# T_TV1_0.net
KiCad netlist of a schematic drawn in EAGLE
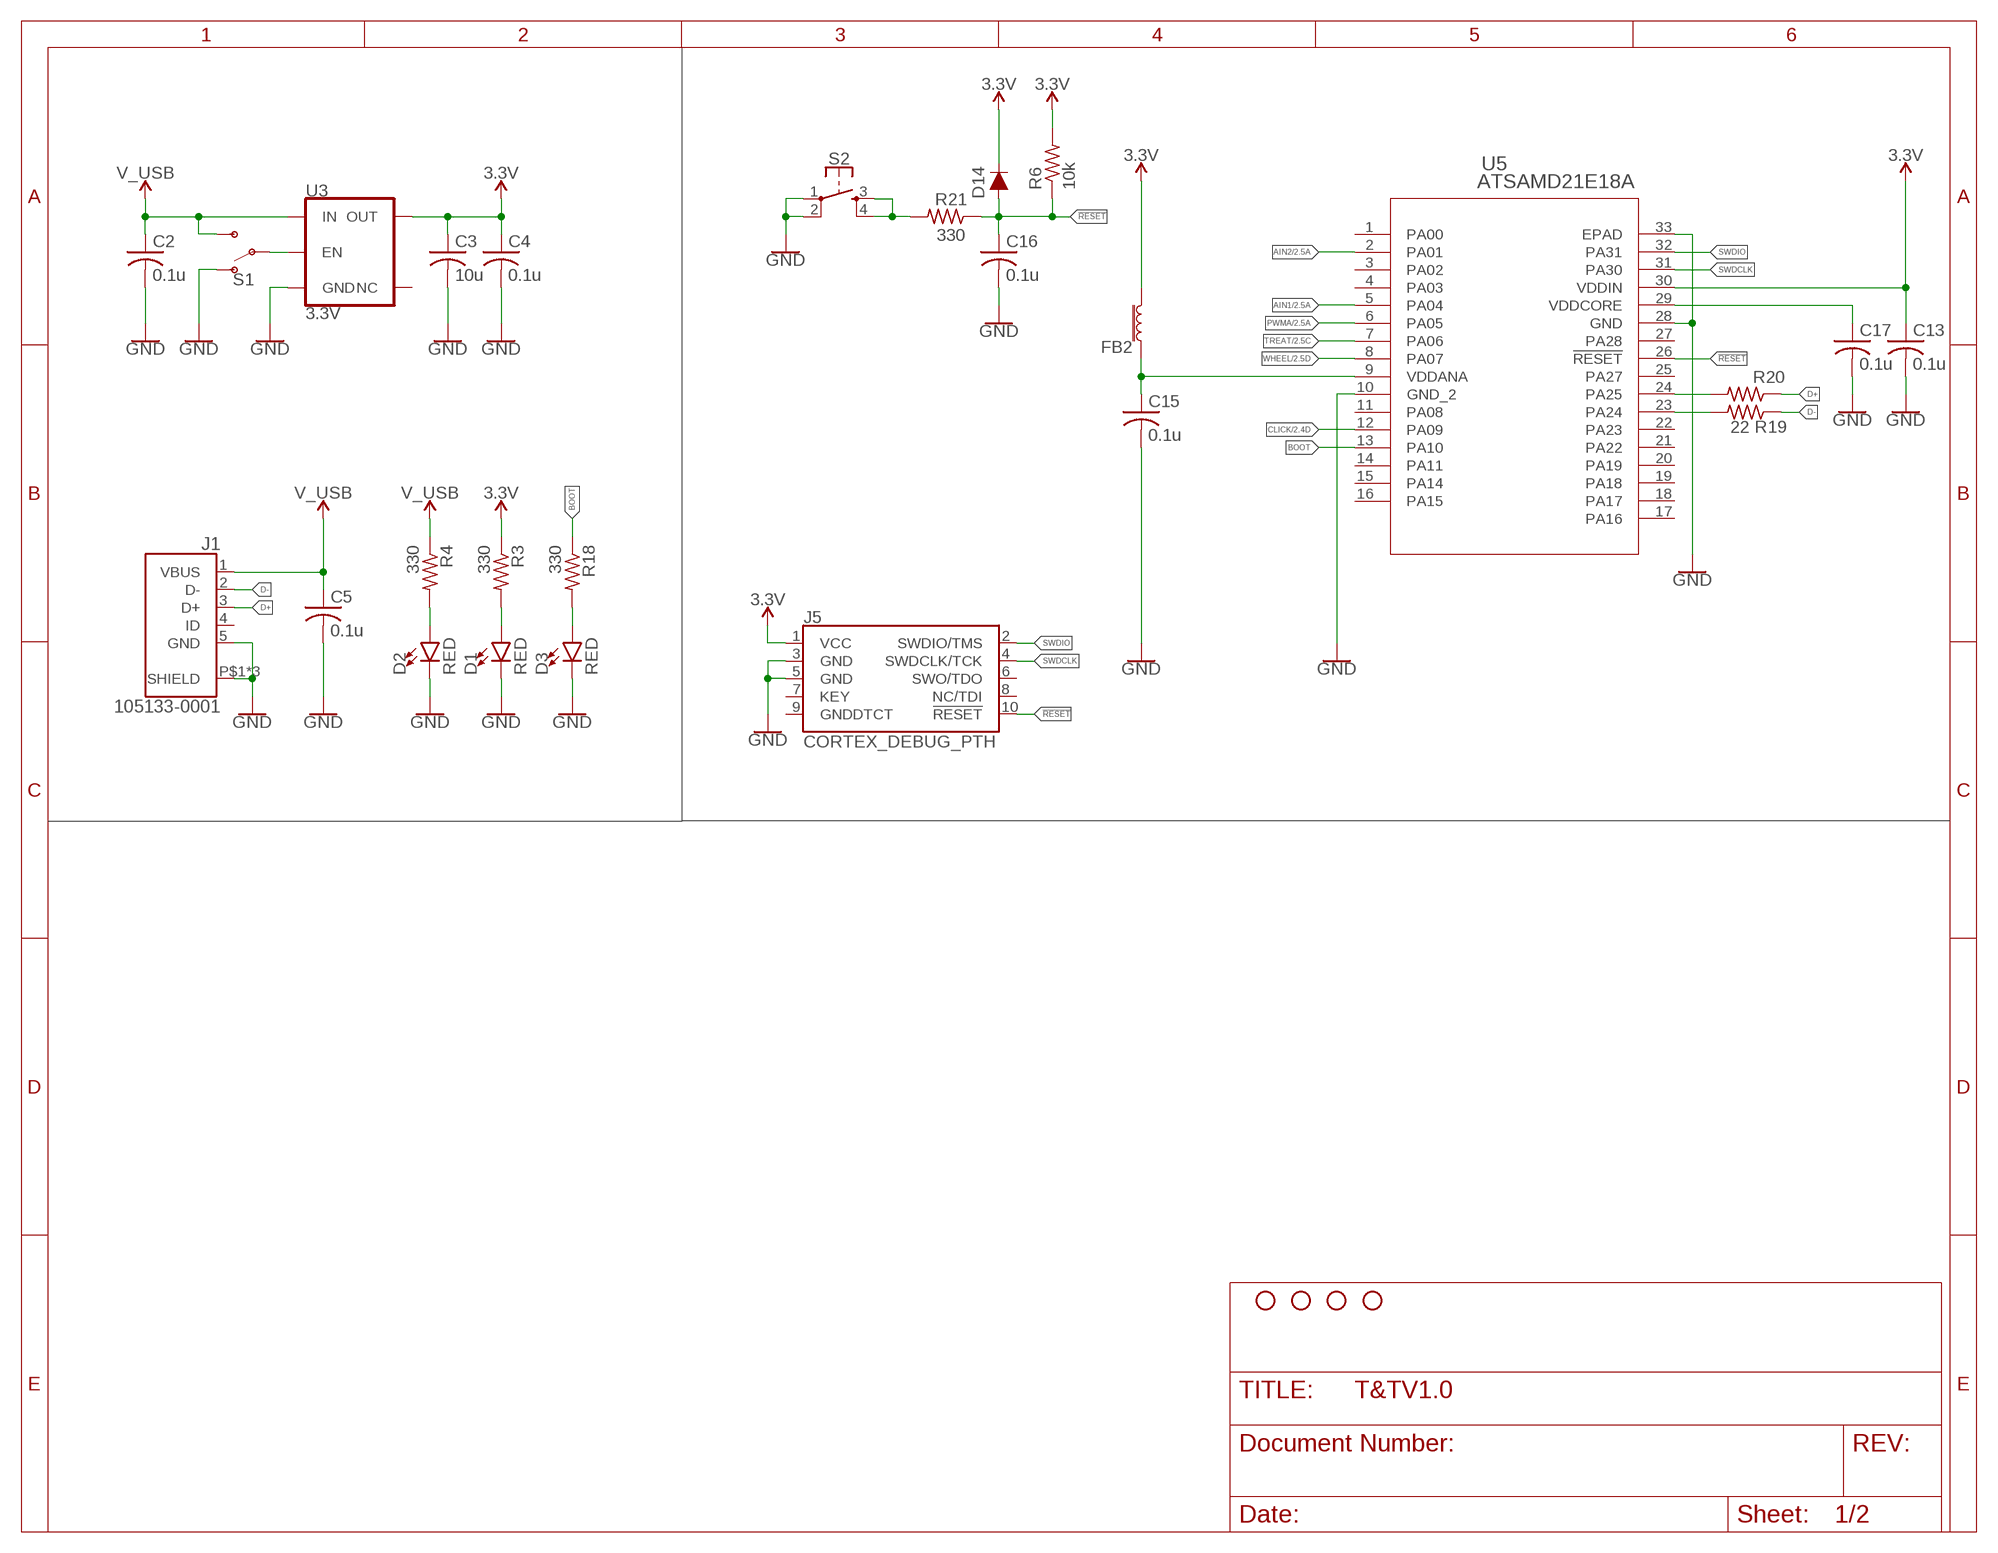
[diagram p0: schematic, sheet 1]
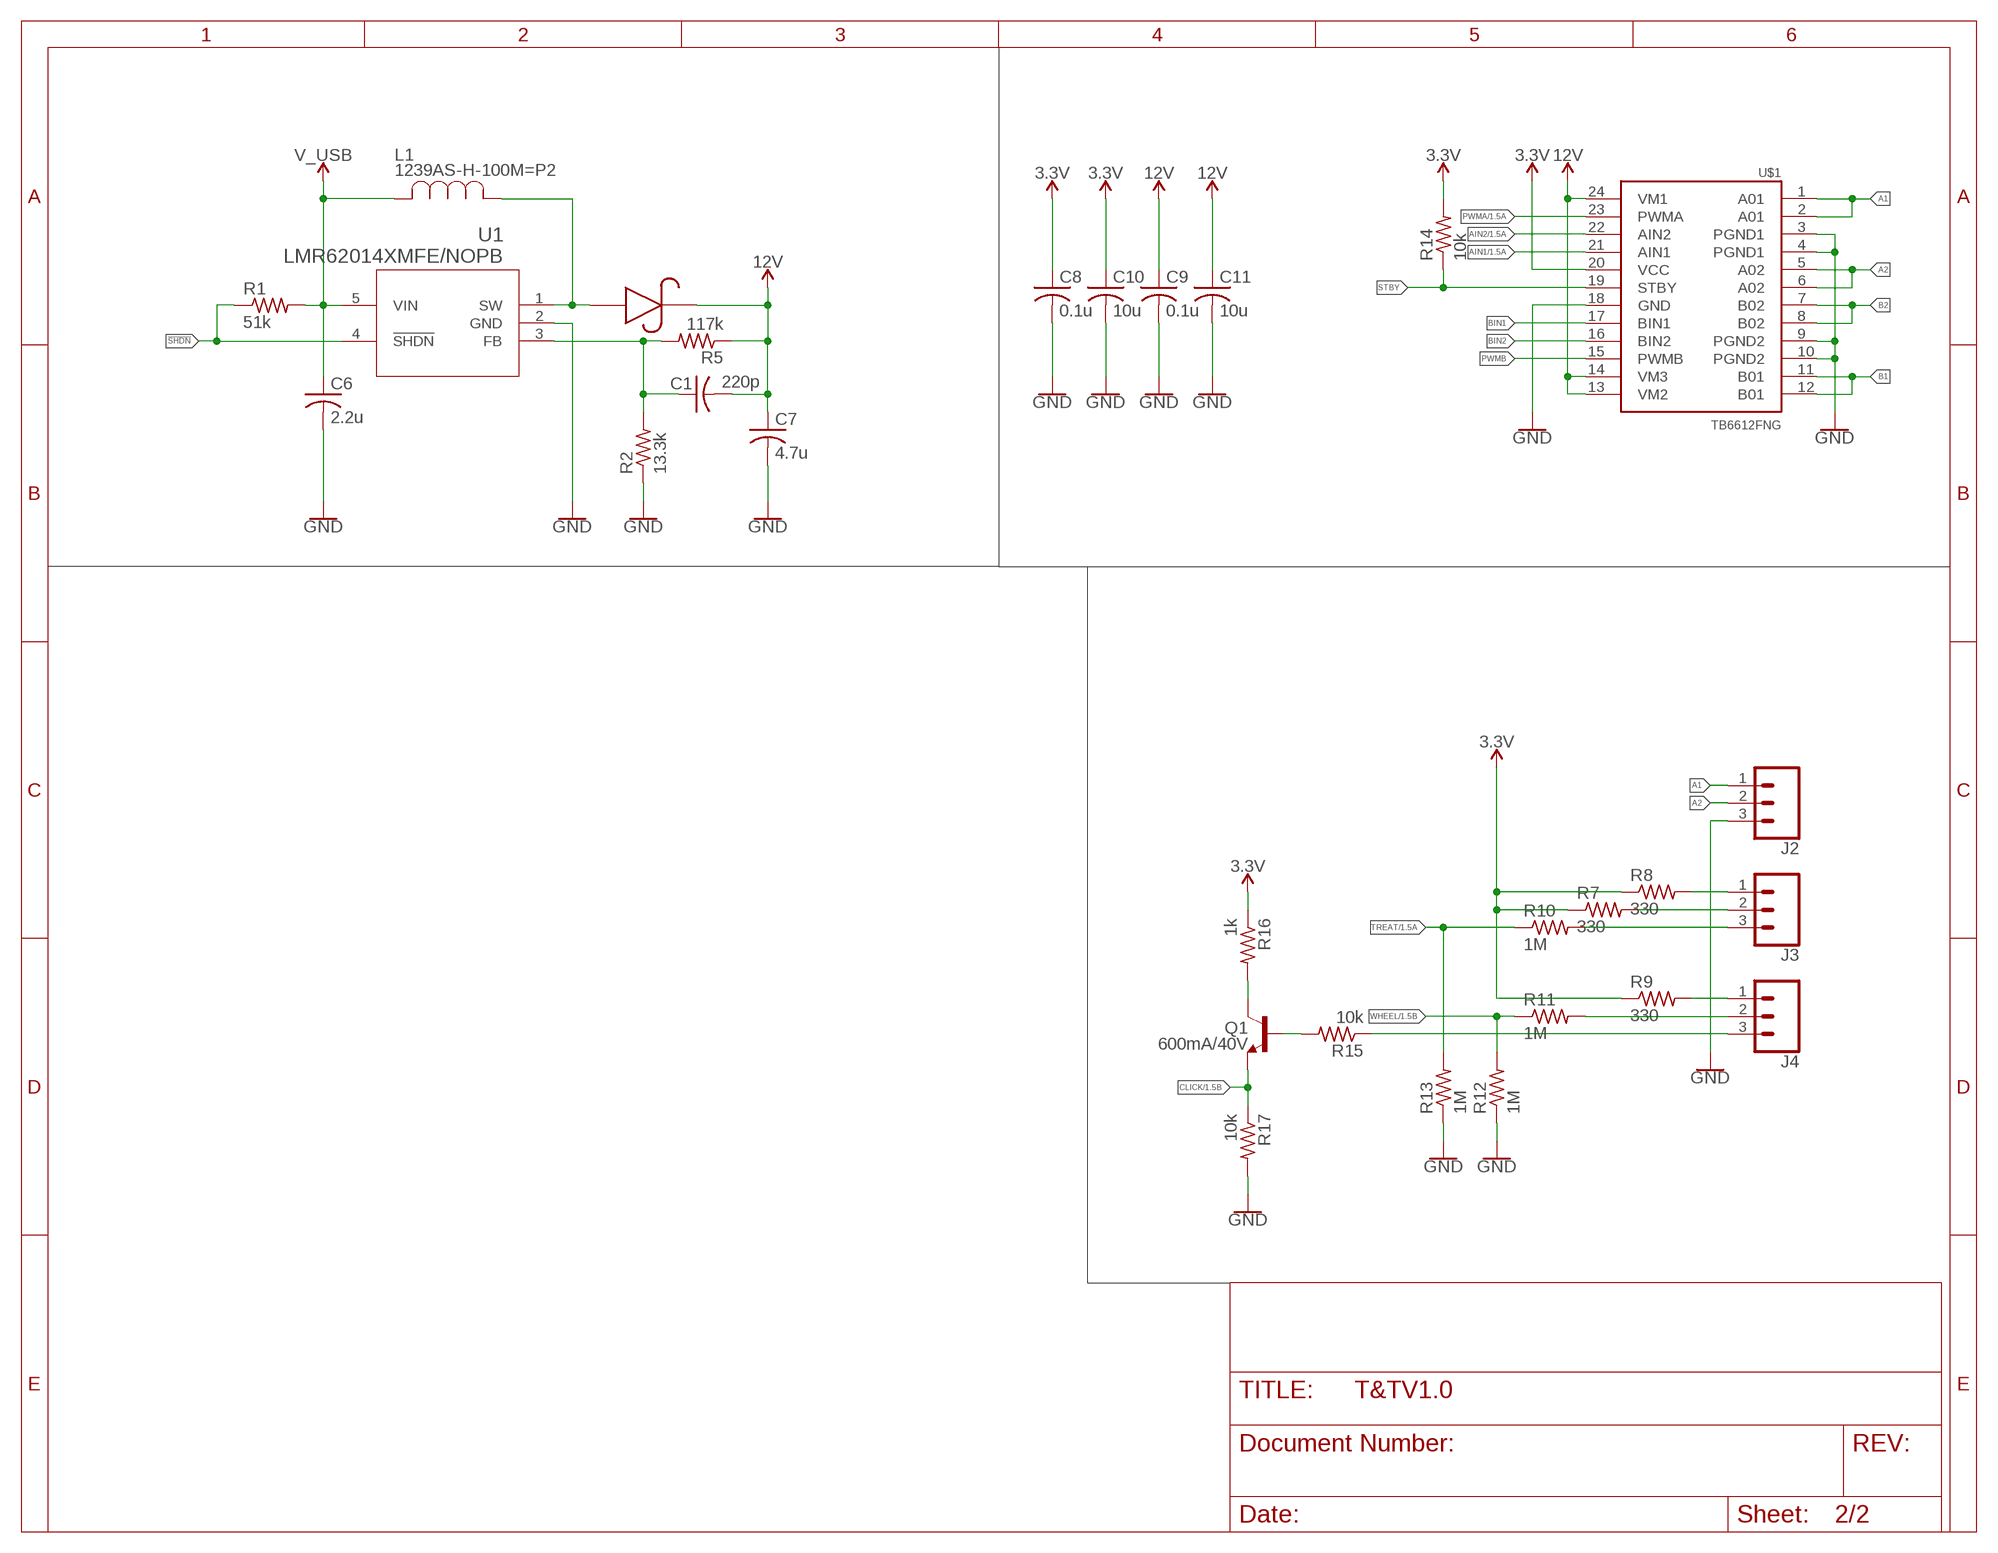
[diagram p1: schematic, sheet 2]

(export (version "E")
  (design (tool "Eeschema 10.0.6"))
  (components
    (comp (ref "C2")
      (value "0.1u")
      (footprint "eagle-import:C0603K")
      (libsource (lib "eagle-import") (part "C-USC0603K"))
    )
    (comp (ref "C3")
      (value "10u")
      (footprint "eagle-import:C1206")
      (libsource (lib "eagle-import") (part "C-USC1206"))
    )
    (comp (ref "C4")
      (value "0.1u")
      (footprint "eagle-import:C0603K")
      (libsource (lib "eagle-import") (part "C-USC0603K"))
    )
    (comp (ref "C5")
      (value "0.1u")
      (footprint "eagle-import:C0603K")
      (libsource (lib "eagle-import") (part "C-USC0603K"))
    )
    (comp (ref "C13")
      (value "0.1u")
      (footprint "eagle-import:C0603K")
      (libsource (lib "eagle-import") (part "C-USC0603K"))
    )
    (comp (ref "C15")
      (value "0.1u")
      (footprint "eagle-import:C0603K")
      (libsource (lib "eagle-import") (part "C-USC0603K"))
    )
    (comp (ref "C16")
      (value "0.1u")
      (footprint "eagle-import:C0603K")
      (libsource (lib "eagle-import") (part "C-USC0603K"))
    )
    (comp (ref "C17")
      (value "0.1u")
      (footprint "eagle-import:C0603K")
      (libsource (lib "eagle-import") (part "C-USC0603K"))
    )
    (comp (ref "D1")
      (value "RED")
      (footprint "eagle-import:LED-0603")
      (libsource (lib "eagle-import") (part "LED-RED0603"))
    )
    (comp (ref "D2")
      (value "RED")
      (footprint "eagle-import:LED-0603")
      (libsource (lib "eagle-import") (part "LED-RED0603"))
    )
    (comp (ref "D3")
      (value "RED")
      (footprint "eagle-import:LED-0603")
      (libsource (lib "eagle-import") (part "LED-RED0603"))
    )
    (comp (ref "D14")
      (value "250mA/100V")
      (footprint "eagle-import:SOD-323")
      (libsource (lib "eagle-import") (part "DIODE-BAS16J"))
    )
    (comp (ref "FB2")
      (value "30Ω/1.8A")
      (footprint "eagle-import:0603")
      (libsource (lib "eagle-import") (part "FERRITE_BEAD-0603"))
    )
    (comp (ref "H1")
      (value "STAND-OFF")
      (footprint "eagle-import:STAND-OFF")
      (libsource (lib "eagle-import") (part "STAND-OFF"))
    )
    (comp (ref "H2")
      (value "STAND-OFF")
      (footprint "eagle-import:STAND-OFF")
      (libsource (lib "eagle-import") (part "STAND-OFF"))
    )
    (comp (ref "H3")
      (value "STAND-OFF")
      (footprint "eagle-import:STAND-OFF")
      (libsource (lib "eagle-import") (part "STAND-OFF"))
    )
    (comp (ref "H4")
      (value "STAND-OFF")
      (footprint "eagle-import:STAND-OFF")
      (libsource (lib "eagle-import") (part "STAND-OFF"))
    )
    (comp (ref "J1")
      (value "105133-0001")
      (footprint "eagle-import:MOLEX_105133-0001")
      (fields
        (field (name "DIGI-KEY_PART_NUMBER") "WM9734CT-ND")
        (field (name "MF") "Molex")
        (field (name "MP") "1051330001")
      )
      (libsource (lib "eagle-import") (part "105133-0001"))
    )
    (comp (ref "J5")
      (value "CORTEX_DEBUG_PTH")
      (footprint "eagle-import:2X5-PTH-1.27MM")
      (libsource (lib "eagle-import") (part "CORTEX_DEBUG_PTH"))
    )
    (comp (ref "R3")
      (value "330")
      (footprint "eagle-import:R0603")
      (libsource (lib "eagle-import") (part "R-US_R0603"))
    )
    (comp (ref "R4")
      (value "330")
      (footprint "eagle-import:R0603")
      (libsource (lib "eagle-import") (part "R-US_R0603"))
    )
    (comp (ref "R6")
      (value "10k")
      (footprint "eagle-import:R0603")
      (libsource (lib "eagle-import") (part "R-US_R0603"))
    )
    (comp (ref "R18")
      (value "330")
      (footprint "eagle-import:R0603")
      (libsource (lib "eagle-import") (part "R-US_R0603"))
    )
    (comp (ref "R19")
      (value "22")
      (footprint "eagle-import:R0603")
      (libsource (lib "eagle-import") (part "R-US_R0603"))
    )
    (comp (ref "R20")
      (value "22")
      (footprint "eagle-import:R0603")
      (libsource (lib "eagle-import") (part "R-US_R0603"))
    )
    (comp (ref "R21")
      (value "330")
      (footprint "eagle-import:R0603")
      (libsource (lib "eagle-import") (part "R-US_R0603"))
    )
    (comp (ref "S1")
      (value "SWITCH-SPDT-SMD-RIGHT-ANGLE")
      (footprint "eagle-import:SWITCH_SPST_SMD_A")
      (libsource (lib "eagle-import") (part "SWITCH-SPDT-SMD-RIGHT-ANGLE"))
    )
    (comp (ref "S2")
      (value "MOMENTARY-SWITCH-SPST-2-SMD-5.2MM")
      (footprint "eagle-import:TACTILE_SWITCH_SMD_5.2MM")
      (libsource (lib "eagle-import") (part "MOMENTARY-SWITCH-SPST-2-SMD-5.2MM"))
    )
    (comp (ref "U3")
      (value "3.3V")
      (footprint "eagle-import:SOT23-5")
      (libsource (lib "eagle-import") (part "V_REG_AP2112K-3.3V"))
    )
    (comp (ref "U5")
      (value "ATSAMD21E18A")
      (footprint "eagle-import:QFN32_5X5MC")
      (fields
        (field (name "MANUFACTURER_PART_NUMBER") "ATSAMD21E18A-MUT")
        (field (name "COPYRIGHT") "Copyright (C) 2018 Accelerated Designs. All rights reserved")
      )
      (libsource (lib "eagle-import") (part "ATSAMD21E18A-MUT"))
    )
    (comp (ref "C1")
      (value "220p")
      (footprint "eagle-import:C0603")
      (libsource (lib "eagle-import") (part "adafruit_420_C-USC0603"))
    )
    (comp (ref "C6")
      (value "2.2u")
      (footprint "eagle-import:C0603")
      (libsource (lib "eagle-import") (part "adafruit_420_C-USC0603"))
    )
    (comp (ref "C7")
      (value "4.7u")
      (footprint "eagle-import:C0603")
      (libsource (lib "eagle-import") (part "adafruit_420_C-USC0603"))
    )
    (comp (ref "C8")
      (value "0.1u")
      (footprint "eagle-import:C0603")
      (libsource (lib "eagle-import") (part "adafruit_420_C-USC0603"))
    )
    (comp (ref "C9")
      (value "0.1u")
      (footprint "eagle-import:C0603")
      (libsource (lib "eagle-import") (part "adafruit_420_C-USC0603"))
    )
    (comp (ref "C10")
      (value "10u")
      (footprint "eagle-import:C1206")
      (libsource (lib "eagle-import") (part "C-USC1206"))
    )
    (comp (ref "C11")
      (value "10u")
      (footprint "eagle-import:C1206")
      (libsource (lib "eagle-import") (part "C-USC1206"))
    )
    (comp (ref "J2")
      (value "CONN_03SCREW-NS")
      (footprint "eagle-import:SCREWTERMINAL-3.5MM-3-NS")
      (libsource (lib "eagle-import") (part "CONN_03SCREW-NS"))
    )
    (comp (ref "J3")
      (value "CONN_03SCREW-NS")
      (footprint "eagle-import:SCREWTERMINAL-3.5MM-3-NS")
      (libsource (lib "eagle-import") (part "CONN_03SCREW-NS"))
    )
    (comp (ref "J4")
      (value "CONN_03SCREW-NS")
      (footprint "eagle-import:SCREWTERMINAL-3.5MM-3-NS")
      (libsource (lib "eagle-import") (part "CONN_03SCREW-NS"))
    )
    (comp (ref "L1")
      (value "1239AS-H-100M=P2")
      (footprint "eagle-import:IND_DFE252012C")
      (fields (field (name "COPYRIGHT") "Copyright (C) 2016 Accelerated Designs. All rights reserved"))
      (libsource (lib "eagle-import") (part "1239AS-H-100M=P2"))
    )
    (comp (ref "Q1")
      (value "600mA/40V")
      (footprint "eagle-import:SOT23-3")
      (libsource (lib "eagle-import") (part "TRANS_NPN-MMBT2222AL"))
    )
    (comp (ref "R1")
      (value "51k")
      (footprint "eagle-import:R0603")
      (libsource (lib "eagle-import") (part "adafruit_420_R-US_R0603"))
    )
    (comp (ref "R2")
      (value "13.3k")
      (footprint "eagle-import:R0603")
      (libsource (lib "eagle-import") (part "adafruit_420_R-US_R0603"))
    )
    (comp (ref "R5")
      (value "117k")
      (footprint "eagle-import:R0603")
      (libsource (lib "eagle-import") (part "adafruit_420_R-US_R0603"))
    )
    (comp (ref "R7")
      (value "330")
      (footprint "eagle-import:R0603")
      (libsource (lib "eagle-import") (part "adafruit_420_R-US_R0603"))
    )
    (comp (ref "R8")
      (value "330")
      (footprint "eagle-import:R0603")
      (libsource (lib "eagle-import") (part "adafruit_420_R-US_R0603"))
    )
    (comp (ref "R9")
      (value "330")
      (footprint "eagle-import:R0603")
      (libsource (lib "eagle-import") (part "adafruit_420_R-US_R0603"))
    )
    (comp (ref "R10")
      (value "1M")
      (footprint "eagle-import:R0603")
      (libsource (lib "eagle-import") (part "adafruit_420_R-US_R0603"))
    )
    (comp (ref "R11")
      (value "1M")
      (footprint "eagle-import:R0603")
      (libsource (lib "eagle-import") (part "adafruit_420_R-US_R0603"))
    )
    (comp (ref "R12")
      (value "1M")
      (footprint "eagle-import:R0603")
      (libsource (lib "eagle-import") (part "adafruit_420_R-US_R0603"))
    )
    (comp (ref "R13")
      (value "1M")
      (footprint "eagle-import:R0603")
      (libsource (lib "eagle-import") (part "adafruit_420_R-US_R0603"))
    )
    (comp (ref "R14")
      (value "10k")
      (footprint "eagle-import:R0603")
      (libsource (lib "eagle-import") (part "adafruit_420_R-US_R0603"))
    )
    (comp (ref "R15")
      (value "10k")
      (footprint "eagle-import:R0603")
      (libsource (lib "eagle-import") (part "adafruit_420_R-US_R0603"))
    )
    (comp (ref "R16")
      (value "1k")
      (footprint "eagle-import:R0603")
      (libsource (lib "eagle-import") (part "adafruit_420_R-US_R0603"))
    )
    (comp (ref "R17")
      (value "10k")
      (footprint "eagle-import:R0603")
      (libsource (lib "eagle-import") (part "adafruit_420_R-US_R0603"))
    )
    (comp (ref "U$1")
      (value "TB6612FNG")
      (footprint "eagle-import:SSOP24")
      (libsource (lib "eagle-import") (part "TB6612FNG"))
    )
    (comp (ref "U1")
      (value "LMR62014XMFE/NOPB")
      (footprint "eagle-import:MF05A")
      (fields (field (name "MANUFACTURER") "Texas Instruments"))
      (libsource (lib "eagle-import") (part "LMR62014XMFE/NOPB"))
    )
    (comp (ref "U4")
      (value "MBR0520")
      (footprint "eagle-import:SOD-123")
      (fields (field (name "MANUFACTURER_PART_NUMBER") "MBR0520LT1G"))
      (libsource (lib "eagle-import") (part "MBR0520LT1G"))
    )
  )
  (nets
    (net (code "1") (name "3.3V") (class "Default")
      (node (ref "C10") (pin "1") (pinfunction "1_1") (pintype "passive"))
      (node (ref "C13") (pin "1") (pinfunction "1_1") (pintype "passive"))
      (node (ref "C3") (pin "1") (pinfunction "1_1") (pintype "passive"))
      (node (ref "C4") (pin "1") (pinfunction "1_1") (pintype "passive"))
      (node (ref "C8") (pin "1") (pinfunction "1_1") (pintype "passive"))
      (node (ref "D14") (pin "C") (pinfunction "C_C") (pintype "passive"))
      (node (ref "FB2") (pin "2") (pinfunction "2_2") (pintype "passive"))
      (node (ref "J5") (pin "1") (pinfunction "VCC_1") (pintype "bidirectional"))
      (node (ref "R14") (pin "2") (pinfunction "2_2") (pintype "passive"))
      (node (ref "R16") (pin "1") (pinfunction "1_1") (pintype "passive"))
      (node (ref "R3") (pin "1") (pinfunction "1_1") (pintype "passive"))
      (node (ref "R6") (pin "2") (pinfunction "2_2") (pintype "passive"))
      (node (ref "R7") (pin "1") (pinfunction "1_1") (pintype "passive"))
      (node (ref "R8") (pin "1") (pinfunction "1_1") (pintype "passive"))
      (node (ref "R9") (pin "1") (pinfunction "1_1") (pintype "passive"))
      (node (ref "U$1") (pin "20") (pinfunction "VCC_20") (pintype "bidirectional"))
      (node (ref "U3") (pin "5") (pinfunction "OUT_5") (pintype "passive"))
      (node (ref "U5") (pin "30") (pinfunction "VDDIN_30") (pintype "power_in"))
    )
    (net (code "2") (name "12V") (class "Default")
      (node (ref "C1") (pin "2") (pinfunction "2_2") (pintype "passive"))
      (node (ref "C11") (pin "1") (pinfunction "1_1") (pintype "passive"))
      (node (ref "C7") (pin "1") (pinfunction "1_1") (pintype "passive"))
      (node (ref "C9") (pin "1") (pinfunction "1_1") (pintype "passive"))
      (node (ref "R5") (pin "1") (pinfunction "1_1") (pintype "passive"))
      (node (ref "U$1") (pin "13") (pinfunction "VM2_13") (pintype "bidirectional"))
      (node (ref "U$1") (pin "14") (pinfunction "VM3_14") (pintype "bidirectional"))
      (node (ref "U$1") (pin "24") (pinfunction "VM1_24") (pintype "bidirectional"))
      (node (ref "U4") (pin "2") (pinfunction "2_2") (pintype "passive"))
    )
    (net (code "3") (name "A1") (class "Default")
      (node (ref "J2") (pin "1") (pinfunction "1_1") (pintype "passive"))
      (node (ref "U$1") (pin "1") (pinfunction "A01_1") (pintype "bidirectional"))
      (node (ref "U$1") (pin "2") (pinfunction "A01_2") (pintype "bidirectional"))
    )
    (net (code "4") (name "A2") (class "Default")
      (node (ref "J2") (pin "2") (pinfunction "2_2") (pintype "passive"))
      (node (ref "U$1") (pin "5") (pinfunction "A02_5") (pintype "bidirectional"))
      (node (ref "U$1") (pin "6") (pinfunction "A02_6") (pintype "bidirectional"))
    )
    (net (code "5") (name "AIN1") (class "Default")
      (node (ref "U$1") (pin "21") (pinfunction "AIN1_21") (pintype "bidirectional"))
      (node (ref "U5") (pin "5") (pinfunction "PA04_5") (pintype "bidirectional"))
    )
    (net (code "6") (name "AIN2") (class "Default")
      (node (ref "U$1") (pin "22") (pinfunction "AIN2_22") (pintype "bidirectional"))
      (node (ref "U5") (pin "2") (pinfunction "PA01_2") (pintype "bidirectional"))
    )
    (net (code "7") (name "B1") (class "Default")
      (node (ref "U$1") (pin "11") (pinfunction "B01_11") (pintype "bidirectional"))
      (node (ref "U$1") (pin "12") (pinfunction "B01_12") (pintype "bidirectional"))
    )
    (net (code "8") (name "B2") (class "Default")
      (node (ref "U$1") (pin "7") (pinfunction "B02_7") (pintype "bidirectional"))
      (node (ref "U$1") (pin "8") (pinfunction "B02_8") (pintype "bidirectional"))
    )
    (net (code "9") (name "BIN1") (class "Default")
      (node (ref "U$1") (pin "17") (pinfunction "BIN1_17") (pintype "bidirectional"))
    )
    (net (code "10") (name "BIN2") (class "Default")
      (node (ref "U$1") (pin "16") (pinfunction "BIN2_16") (pintype "bidirectional"))
    )
    (net (code "11") (name "BOOT") (class "Default")
      (node (ref "R18") (pin "1") (pinfunction "1_1") (pintype "passive"))
      (node (ref "U5") (pin "13") (pinfunction "PA10_13") (pintype "bidirectional"))
    )
    (net (code "12") (name "CLICK") (class "Default")
      (node (ref "Q1") (pin "2") (pinfunction "E_2") (pintype "passive"))
      (node (ref "R17") (pin "1") (pinfunction "1_1") (pintype "passive"))
      (node (ref "U5") (pin "12") (pinfunction "PA09_12") (pintype "bidirectional"))
    )
    (net (code "13") (name "D+") (class "Default")
      (node (ref "J1") (pin "3") (pinfunction "D+_3") (pintype "bidirectional"))
      (node (ref "R20") (pin "1") (pinfunction "1_1") (pintype "passive"))
    )
    (net (code "14") (name "D-") (class "Default")
      (node (ref "J1") (pin "2") (pinfunction "D-_2") (pintype "bidirectional"))
      (node (ref "R19") (pin "1") (pinfunction "1_1") (pintype "passive"))
    )
    (net (code "15") (name "GND") (class "Default")
      (node (ref "C10") (pin "2") (pinfunction "2_2") (pintype "passive"))
      (node (ref "C11") (pin "2") (pinfunction "2_2") (pintype "passive"))
      (node (ref "C13") (pin "2") (pinfunction "2_2") (pintype "passive"))
      (node (ref "C15") (pin "2") (pinfunction "2_2") (pintype "passive"))
      (node (ref "C16") (pin "2") (pinfunction "2_2") (pintype "passive"))
      (node (ref "C17") (pin "2") (pinfunction "2_2") (pintype "passive"))
      (node (ref "C2") (pin "2") (pinfunction "2_2") (pintype "passive"))
      (node (ref "C3") (pin "2") (pinfunction "2_2") (pintype "passive"))
      (node (ref "C4") (pin "2") (pinfunction "2_2") (pintype "passive"))
      (node (ref "C5") (pin "2") (pinfunction "2_2") (pintype "passive"))
      (node (ref "C6") (pin "2") (pinfunction "2_2") (pintype "passive"))
      (node (ref "C7") (pin "2") (pinfunction "2_2") (pintype "passive"))
      (node (ref "C8") (pin "2") (pinfunction "2_2") (pintype "passive"))
      (node (ref "C9") (pin "2") (pinfunction "2_2") (pintype "passive"))
      (node (ref "D1") (pin "C") (pinfunction "C_C") (pintype "passive"))
      (node (ref "D2") (pin "C") (pinfunction "C_C") (pintype "passive"))
      (node (ref "D3") (pin "C") (pinfunction "C_C") (pintype "passive"))
      (node (ref "J1") (pin "5") (pinfunction "GND_5") (pintype "power_in"))
      (node (ref "J1") (pin "P$1") (pinfunction "SHIELD_P$1") (pintype "passive"))
      (node (ref "J1") (pin "P$2") (pinfunction "SHIELD_P$2") (pintype "passive"))
      (node (ref "J1") (pin "P$3") (pinfunction "SHIELD_P$3") (pintype "passive"))
      (node (ref "J2") (pin "3") (pinfunction "3_3") (pintype "passive"))
      (node (ref "J5") (pin "3") (pinfunction "GND_3") (pintype "bidirectional"))
      (node (ref "J5") (pin "5") (pinfunction "GND_5") (pintype "bidirectional"))
      (node (ref "R12") (pin "1") (pinfunction "1_1") (pintype "passive"))
      (node (ref "R13") (pin "1") (pinfunction "1_1") (pintype "passive"))
      (node (ref "R17") (pin "2") (pinfunction "2_2") (pintype "passive"))
      (node (ref "R2") (pin "1") (pinfunction "1_1") (pintype "passive"))
      (node (ref "S1") (pin "1") (pinfunction "O_1") (pintype "passive"))
      (node (ref "S2") (pin "1") (pinfunction "1_1") (pintype "passive"))
      (node (ref "S2") (pin "2") (pinfunction "2_2") (pintype "passive"))
      (node (ref "U$1") (pin "10") (pinfunction "PGND2_10") (pintype "bidirectional"))
      (node (ref "U$1") (pin "18") (pinfunction "GND_18") (pintype "bidirectional"))
      (node (ref "U$1") (pin "3") (pinfunction "PGND1_3") (pintype "bidirectional"))
      (node (ref "U$1") (pin "4") (pinfunction "PGND1_4") (pintype "bidirectional"))
      (node (ref "U$1") (pin "9") (pinfunction "PGND2_9") (pintype "bidirectional"))
      (node (ref "U1") (pin "2") (pinfunction "GND_2") (pintype "power_in"))
      (node (ref "U3") (pin "2") (pinfunction "GND_2") (pintype "input"))
      (node (ref "U5") (pin "10") (pinfunction "GND_2_10") (pintype "passive"))
      (node (ref "U5") (pin "28") (pinfunction "GND_28") (pintype "passive"))
      (node (ref "U5") (pin "33") (pinfunction "EPAD_33") (pintype "passive"))
    )
    (net (code "16") (name "Net-(D1-PadA)") (class "Default")
      (node (ref "D1") (pin "A") (pinfunction "A_A") (pintype "passive"))
      (node (ref "R3") (pin "2") (pinfunction "2_2") (pintype "passive"))
    )
    (net (code "17") (name "Net-(D2-PadA)") (class "Default")
      (node (ref "D2") (pin "A") (pinfunction "A_A") (pintype "passive"))
      (node (ref "R4") (pin "2") (pinfunction "2_2") (pintype "passive"))
    )
    (net (code "18") (name "Net-(D3-PadA)") (class "Default")
      (node (ref "D3") (pin "A") (pinfunction "A_A") (pintype "passive"))
      (node (ref "R18") (pin "2") (pinfunction "2_2") (pintype "passive"))
    )
    (net (code "19") (name "Net-(J3-Pad1)") (class "Default")
      (node (ref "J3") (pin "1") (pinfunction "1_1") (pintype "passive"))
      (node (ref "R8") (pin "2") (pinfunction "2_2") (pintype "passive"))
    )
    (net (code "20") (name "Net-(J3-Pad2)") (class "Default")
      (node (ref "J3") (pin "2") (pinfunction "2_2") (pintype "passive"))
      (node (ref "R7") (pin "2") (pinfunction "2_2") (pintype "passive"))
    )
    (net (code "21") (name "Net-(J3-Pad3)") (class "Default")
      (node (ref "J3") (pin "3") (pinfunction "3_3") (pintype "passive"))
      (node (ref "R10") (pin "2") (pinfunction "2_2") (pintype "passive"))
    )
    (net (code "22") (name "Net-(J4-Pad1)") (class "Default")
      (node (ref "J4") (pin "1") (pinfunction "1_1") (pintype "passive"))
      (node (ref "R9") (pin "2") (pinfunction "2_2") (pintype "passive"))
    )
    (net (code "23") (name "Net-(J4-Pad2)") (class "Default")
      (node (ref "J4") (pin "2") (pinfunction "2_2") (pintype "passive"))
      (node (ref "R11") (pin "2") (pinfunction "2_2") (pintype "passive"))
    )
    (net (code "24") (name "Net-(J4-Pad3)") (class "Default")
      (node (ref "J4") (pin "3") (pinfunction "3_3") (pintype "passive"))
      (node (ref "R15") (pin "1") (pinfunction "1_1") (pintype "passive"))
    )
    (net (code "25") (name "Net-(Q1-B)") (class "Default")
      (node (ref "Q1") (pin "1") (pinfunction "B_1") (pintype "passive"))
      (node (ref "R15") (pin "2") (pinfunction "2_2") (pintype "passive"))
    )
    (net (code "26") (name "Net-(Q1-C)") (class "Default")
      (node (ref "Q1") (pin "3") (pinfunction "C_3") (pintype "passive"))
      (node (ref "R16") (pin "2") (pinfunction "2_2") (pintype "passive"))
    )
    (net (code "27") (name "Net-(R21-Pad2)") (class "Default")
      (node (ref "R21") (pin "2") (pinfunction "2_2") (pintype "passive"))
      (node (ref "S2") (pin "3") (pinfunction "3_3") (pintype "passive"))
      (node (ref "S2") (pin "4") (pinfunction "4_4") (pintype "passive"))
    )
    (net (code "28") (name "Net-(S1-P)") (class "Default")
      (node (ref "S1") (pin "2") (pinfunction "P_2") (pintype "passive"))
      (node (ref "U3") (pin "3") (pinfunction "EN_3") (pintype "input"))
    )
    (net (code "29") (name "Net-(U1-FB)") (class "Default")
      (node (ref "C1") (pin "1") (pinfunction "1_1") (pintype "passive"))
      (node (ref "R2") (pin "2") (pinfunction "2_2") (pintype "passive"))
      (node (ref "R5") (pin "2") (pinfunction "2_2") (pintype "passive"))
      (node (ref "U1") (pin "3") (pinfunction "FB_3") (pintype "passive"))
    )
    (net (code "30") (name "Net-(U1-SW)") (class "Default")
      (node (ref "L1") (pin "1") (pinfunction "1_1") (pintype "passive"))
      (node (ref "U1") (pin "1") (pinfunction "SW_1") (pintype "passive"))
      (node (ref "U4") (pin "1") (pinfunction "1_1") (pintype "passive"))
    )
    (net (code "31") (name "Net-(U5-PA24)") (class "Default")
      (node (ref "R19") (pin "2") (pinfunction "2_2") (pintype "passive"))
      (node (ref "U5") (pin "23") (pinfunction "PA24_23") (pintype "bidirectional"))
    )
    (net (code "32") (name "Net-(U5-PA25)") (class "Default")
      (node (ref "R20") (pin "2") (pinfunction "2_2") (pintype "passive"))
      (node (ref "U5") (pin "24") (pinfunction "PA25_24") (pintype "bidirectional"))
    )
    (net (code "33") (name "Net-(U5-VDDANA)") (class "Default")
      (node (ref "C15") (pin "1") (pinfunction "1_1") (pintype "passive"))
      (node (ref "FB2") (pin "1") (pinfunction "1_1") (pintype "passive"))
      (node (ref "U5") (pin "9") (pinfunction "VDDANA_9") (pintype "power_in"))
    )
    (net (code "34") (name "Net-(U5-VDDCORE)") (class "Default")
      (node (ref "C17") (pin "1") (pinfunction "1_1") (pintype "passive"))
      (node (ref "U5") (pin "29") (pinfunction "VDDCORE_29") (pintype "power_in"))
    )
    (net (code "35") (name "PWMA") (class "Default")
      (node (ref "U$1") (pin "23") (pinfunction "PWMA_23") (pintype "bidirectional"))
      (node (ref "U5") (pin "6") (pinfunction "PA05_6") (pintype "bidirectional"))
    )
    (net (code "36") (name "PWMB") (class "Default")
      (node (ref "U$1") (pin "15") (pinfunction "PWMB_15") (pintype "bidirectional"))
    )
    (net (code "37") (name "STBY") (class "Default")
      (node (ref "R14") (pin "1") (pinfunction "1_1") (pintype "passive"))
      (node (ref "U$1") (pin "19") (pinfunction "STBY_19") (pintype "bidirectional"))
    )
    (net (code "38") (name "SWDCLK") (class "Default")
      (node (ref "J5") (pin "4") (pinfunction "SWDCLK/TCK_4") (pintype "bidirectional"))
      (node (ref "U5") (pin "31") (pinfunction "PA30_31") (pintype "bidirectional"))
    )
    (net (code "39") (name "SWDIO") (class "Default")
      (node (ref "J5") (pin "2") (pinfunction "SWDIO/TMS_2") (pintype "bidirectional"))
      (node (ref "U5") (pin "32") (pinfunction "PA31_32") (pintype "bidirectional"))
    )
    (net (code "40") (name "TREAT") (class "Default")
      (node (ref "R10") (pin "1") (pinfunction "1_1") (pintype "passive"))
      (node (ref "R13") (pin "2") (pinfunction "2_2") (pintype "passive"))
      (node (ref "U5") (pin "7") (pinfunction "PA06_7") (pintype "bidirectional"))
    )
    (net (code "41") (name "V_USB") (class "Default")
      (node (ref "C2") (pin "1") (pinfunction "1_1") (pintype "passive"))
      (node (ref "C5") (pin "1") (pinfunction "1_1") (pintype "passive"))
      (node (ref "C6") (pin "1") (pinfunction "1_1") (pintype "passive"))
      (node (ref "J1") (pin "1") (pinfunction "VBUS_1") (pintype "power_in"))
      (node (ref "L1") (pin "2") (pinfunction "2_2") (pintype "passive"))
      (node (ref "R1") (pin "2") (pinfunction "2_2") (pintype "passive"))
      (node (ref "R4") (pin "1") (pinfunction "1_1") (pintype "passive"))
      (node (ref "S1") (pin "3") (pinfunction "S_3") (pintype "passive"))
      (node (ref "U1") (pin "5") (pinfunction "VIN_5") (pintype "input"))
      (node (ref "U3") (pin "1") (pinfunction "IN_1") (pintype "input"))
    )
    (net (code "42") (name "WHEEL") (class "Default")
      (node (ref "R11") (pin "1") (pinfunction "1_1") (pintype "passive"))
      (node (ref "R12") (pin "2") (pinfunction "2_2") (pintype "passive"))
      (node (ref "U5") (pin "8") (pinfunction "PA07_8") (pintype "bidirectional"))
    )
    (net (code "43") (name "unconnected-(J1-ID-Pad4)") (class "Default")
      (node (ref "J1") (pin "4") (pinfunction "ID_4") (pintype "input"))
    )
    (net (code "44") (name "unconnected-(J5-GNDDTCT-Pad9)") (class "Default")
      (node (ref "J5") (pin "9") (pinfunction "GNDDTCT_9") (pintype "bidirectional"))
    )
    (net (code "45") (name "unconnected-(J5-KEY-Pad7)") (class "Default")
      (node (ref "J5") (pin "7") (pinfunction "KEY_7") (pintype "bidirectional"))
    )
    (net (code "46") (name "unconnected-(J5-NC{slash}TDI-Pad8)") (class "Default")
      (node (ref "J5") (pin "8") (pinfunction "NC/TDI_8") (pintype "bidirectional"))
    )
    (net (code "47") (name "unconnected-(J5-SWO{slash}TDO-Pad6)") (class "Default")
      (node (ref "J5") (pin "6") (pinfunction "SWO/TDO_6") (pintype "bidirectional"))
    )
    (net (code "48") (name "unconnected-(U3-NC-Pad4)") (class "Default")
      (node (ref "U3") (pin "4") (pinfunction "NC_4") (pintype "no_connect"))
    )
    (net (code "49") (name "unconnected-(U5-PA00-Pad1)") (class "Default")
      (node (ref "U5") (pin "1") (pinfunction "PA00_1") (pintype "bidirectional"))
    )
    (net (code "50") (name "unconnected-(U5-PA02-Pad3)") (class "Default")
      (node (ref "U5") (pin "3") (pinfunction "PA02_3") (pintype "bidirectional"))
    )
    (net (code "51") (name "unconnected-(U5-PA03-Pad4)") (class "Default")
      (node (ref "U5") (pin "4") (pinfunction "PA03_4") (pintype "bidirectional"))
    )
    (net (code "52") (name "unconnected-(U5-PA08-Pad11)") (class "Default")
      (node (ref "U5") (pin "11") (pinfunction "PA08_11") (pintype "bidirectional"))
    )
    (net (code "53") (name "unconnected-(U5-PA11-Pad14)") (class "Default")
      (node (ref "U5") (pin "14") (pinfunction "PA11_14") (pintype "bidirectional"))
    )
    (net (code "54") (name "unconnected-(U5-PA14-Pad15)") (class "Default")
      (node (ref "U5") (pin "15") (pinfunction "PA14_15") (pintype "bidirectional"))
    )
    (net (code "55") (name "unconnected-(U5-PA15-Pad16)") (class "Default")
      (node (ref "U5") (pin "16") (pinfunction "PA15_16") (pintype "bidirectional"))
    )
    (net (code "56") (name "unconnected-(U5-PA16-Pad17)") (class "Default")
      (node (ref "U5") (pin "17") (pinfunction "PA16_17") (pintype "bidirectional"))
    )
    (net (code "57") (name "unconnected-(U5-PA17-Pad18)") (class "Default")
      (node (ref "U5") (pin "18") (pinfunction "PA17_18") (pintype "bidirectional"))
    )
    (net (code "58") (name "unconnected-(U5-PA18-Pad19)") (class "Default")
      (node (ref "U5") (pin "19") (pinfunction "PA18_19") (pintype "bidirectional"))
    )
    (net (code "59") (name "unconnected-(U5-PA19-Pad20)") (class "Default")
      (node (ref "U5") (pin "20") (pinfunction "PA19_20") (pintype "bidirectional"))
    )
    (net (code "60") (name "unconnected-(U5-PA22-Pad21)") (class "Default")
      (node (ref "U5") (pin "21") (pinfunction "PA22_21") (pintype "bidirectional"))
    )
    (net (code "61") (name "unconnected-(U5-PA23-Pad22)") (class "Default")
      (node (ref "U5") (pin "22") (pinfunction "PA23_22") (pintype "bidirectional"))
    )
    (net (code "62") (name "unconnected-(U5-PA27-Pad25)") (class "Default")
      (node (ref "U5") (pin "25") (pinfunction "PA27_25") (pintype "bidirectional"))
    )
    (net (code "63") (name "unconnected-(U5-PA28-Pad27)") (class "Default")
      (node (ref "U5") (pin "27") (pinfunction "PA28_27") (pintype "bidirectional"))
    )
    (net (code "64") (name "~{RESET}") (class "Default")
      (node (ref "C16") (pin "1") (pinfunction "1_1") (pintype "passive"))
      (node (ref "D14") (pin "A") (pinfunction "A_A") (pintype "passive"))
      (node (ref "J5") (pin "10") (pinfunction "~{RESET}_10") (pintype "bidirectional"))
      (node (ref "R21") (pin "1") (pinfunction "1_1") (pintype "passive"))
      (node (ref "R6") (pin "1") (pinfunction "1_1") (pintype "passive"))
      (node (ref "U5") (pin "26") (pinfunction "~{RESET}_26") (pintype "passive"))
    )
    (net (code "65") (name "~{SHDN}") (class "Default")
      (node (ref "R1") (pin "1") (pinfunction "1_1") (pintype "passive"))
      (node (ref "U1") (pin "4") (pinfunction "~{SHDN}_4") (pintype "input"))
    )
  )
)
